# tilt_brick.net
KiCad netlist of a schematic drawn in EAGLE
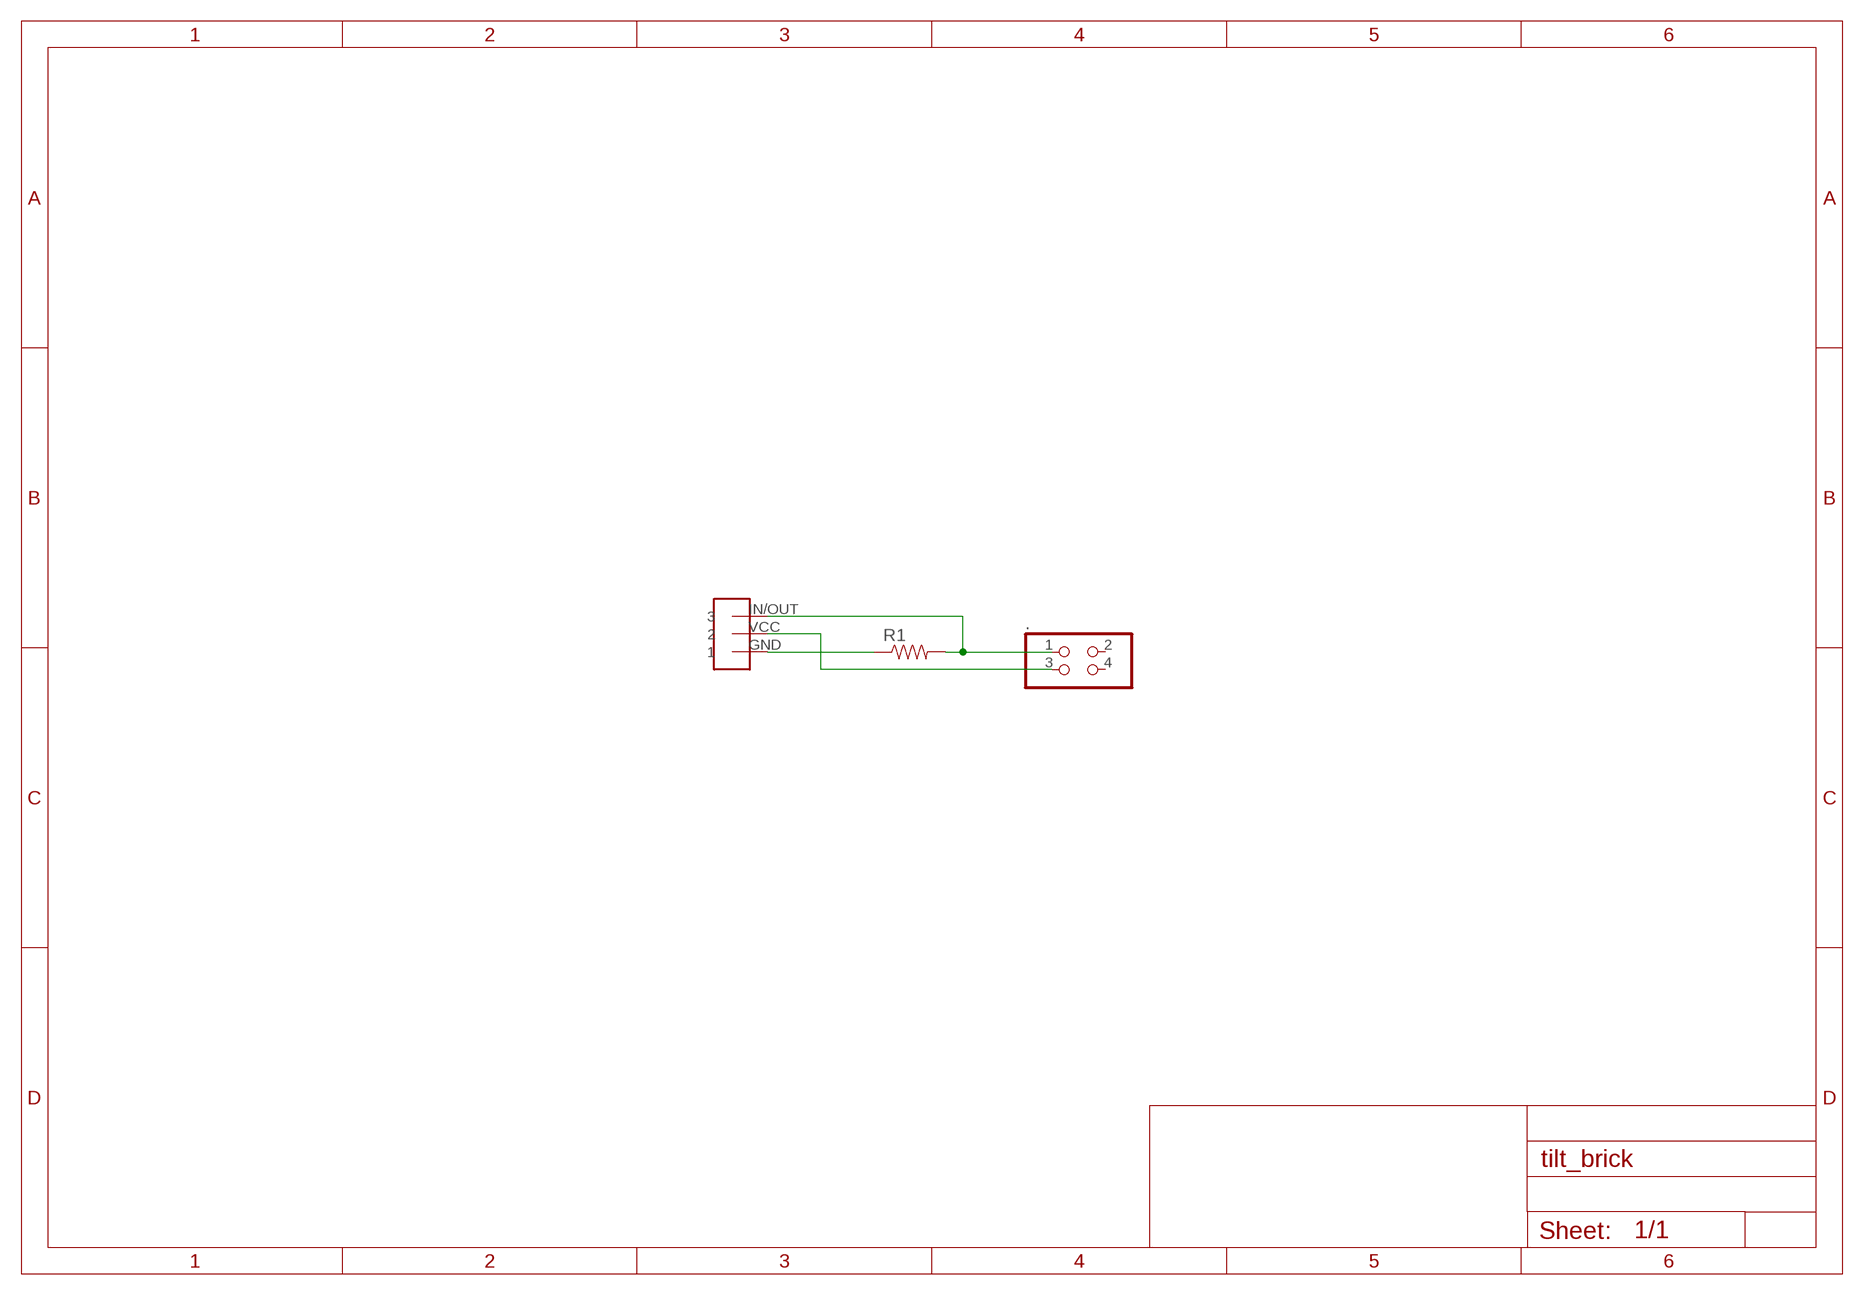
[diagram p0: schematic, sheet 1]

(export (version "E")
  (design (tool "Eeschema 10.0.6"))
  (components
    (comp (ref ".")
      (value "PINHD-2X2")
      (footprint "eagle-import:2X02")
      (libsource (lib "eagle-import") (part "PINHD-2X2"))
    )
    (comp (ref "R1")
      (value "RESISTORKIT")
      (footprint "eagle-import:AXIAL-0.3-KIT")
      (libsource (lib "eagle-import") (part "RESISTORKIT"))
    )
    (comp (ref "U$1")
      (value "BRICK-3PIN")
      (footprint "eagle-import:BRICK_3PIN")
      (libsource (lib "eagle-import") (part "BRICK-3PIN"))
    )
  )
  (nets
    (net (code "1") (name "Net-(R1-1)") (class "Default")
      (node (ref "R1") (pin "P$1") (pinfunction "1_P$1") (pintype "passive"))
      (node (ref "U$1") (pin "GND") (pinfunction "1_GND") (pintype "bidirectional"))
    )
    (net (code "2") (name "Net-(R1-2)") (class "Default")
      (node (ref ".") (pin "1") (pinfunction "1_1") (pintype "passive"))
      (node (ref "R1") (pin "P$2") (pinfunction "2_P$2") (pintype "passive"))
      (node (ref "U$1") (pin "IN/OUT") (pinfunction "3_IN/OUT") (pintype "bidirectional"))
    )
    (net (code "3") (name "Net-(U$1-2)") (class "Default")
      (node (ref ".") (pin "3") (pinfunction "3_3") (pintype "passive"))
      (node (ref "U$1") (pin "VCC") (pinfunction "2_VCC") (pintype "bidirectional"))
    )
    (net (code "4") (name "unconnected-(.-Pad2)") (class "Default")
      (node (ref ".") (pin "2") (pinfunction "2_2") (pintype "passive"))
    )
    (net (code "5") (name "unconnected-(.-Pad4)") (class "Default")
      (node (ref ".") (pin "4") (pinfunction "4_4") (pintype "passive"))
    )
  )
)
